# 7seg.net
KiCad netlist of a schematic drawn in Altium Designer
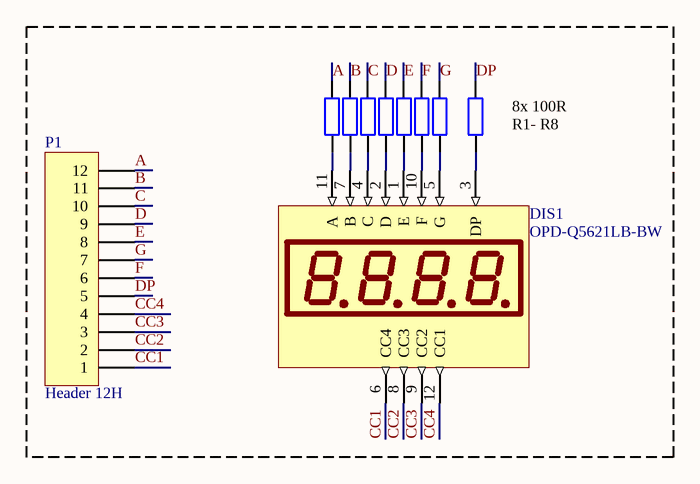
[diagram p0: 7seg.SchDoc]

(export (version "E")
  (design (tool "Eeschema 10.0.6"))
  (components
    (comp (ref "DIS1")
      (value "OPD-Q5621LB-BW")
      (footprint "OPD-Q5621LB-BW")
      (description "Wyświetlacz: LED; 7-segmentowy; 14,2mm; niebieski; 80mcd; katoda")
      (libsource (lib "Library") (part "OPD-Q5621LB-BW"))
    )
    (comp (ref "P1")
      (value "Header 12H")
      (footprint "MA12-1L")
      (description "Header, 12-Pin, Right Angle")
      (libsource (lib "Connectors") (part "Header 12H"))
    )
    (comp (ref "R1")
      (value "100R")
      (footprint "R0805")
      (description "Resistor")
      (libsource (lib "altium-import") (part "root_1_Res_"))
    )
    (comp (ref "R2")
      (value "100R")
      (footprint "R0805")
      (description "Resistor")
      (libsource (lib "altium-import") (part "root_1_Res_"))
    )
    (comp (ref "R3")
      (value "100R")
      (footprint "R0805")
      (description "Resistor")
      (libsource (lib "altium-import") (part "root_1_Res_"))
    )
    (comp (ref "R4")
      (value "100R")
      (footprint "R0805")
      (description "Resistor")
      (libsource (lib "altium-import") (part "root_1_Res_"))
    )
    (comp (ref "R5")
      (value "100R")
      (footprint "R0805")
      (description "Resistor")
      (libsource (lib "altium-import") (part "root_1_Res_"))
    )
    (comp (ref "R6")
      (value "100R")
      (footprint "R0805")
      (description "Resistor")
      (libsource (lib "altium-import") (part "root_1_Res_"))
    )
    (comp (ref "R7")
      (value "100R")
      (footprint "R0805")
      (description "Resistor")
      (libsource (lib "altium-import") (part "root_1_Res_"))
    )
    (comp (ref "R8")
      (value "100R")
      (footprint "R0805")
      (description "Resistor")
      (libsource (lib "altium-import") (part "root_1_Res_"))
    )
  )
  (nets
    (net (code "1") (name "/A") (class "Default")
      (node (ref "P1") (pin "12") (pinfunction "12_12") (pintype "passive"))
      (node (ref "R1") (pin "2") (pinfunction "2_2") (pintype "passive"))
    )
    (net (code "2") (name "/B") (class "Default")
      (node (ref "P1") (pin "11") (pinfunction "11_11") (pintype "passive"))
      (node (ref "R2") (pin "2") (pinfunction "2_2") (pintype "passive"))
    )
    (net (code "3") (name "/C") (class "Default")
      (node (ref "P1") (pin "10") (pinfunction "10_10") (pintype "passive"))
      (node (ref "R3") (pin "2") (pinfunction "2_2") (pintype "passive"))
    )
    (net (code "4") (name "/CC1") (class "Default")
      (node (ref "DIS1") (pin "6") (pinfunction "CC4_6") (pintype "output"))
      (node (ref "P1") (pin "1") (pinfunction "1_1") (pintype "passive"))
    )
    (net (code "5") (name "/CC2") (class "Default")
      (node (ref "DIS1") (pin "8") (pinfunction "CC3_8") (pintype "output"))
      (node (ref "P1") (pin "2") (pinfunction "2_2") (pintype "passive"))
    )
    (net (code "6") (name "/CC3") (class "Default")
      (node (ref "DIS1") (pin "9") (pinfunction "CC2_9") (pintype "output"))
      (node (ref "P1") (pin "3") (pinfunction "3_3") (pintype "passive"))
    )
    (net (code "7") (name "/CC4") (class "Default")
      (node (ref "DIS1") (pin "12") (pinfunction "CC1_12") (pintype "output"))
      (node (ref "P1") (pin "4") (pinfunction "4_4") (pintype "passive"))
    )
    (net (code "8") (name "/D") (class "Default")
      (node (ref "P1") (pin "9") (pinfunction "9_9") (pintype "passive"))
      (node (ref "R4") (pin "2") (pinfunction "2_2") (pintype "passive"))
    )
    (net (code "9") (name "/DP") (class "Default")
      (node (ref "P1") (pin "5") (pinfunction "5_5") (pintype "passive"))
      (node (ref "R8") (pin "2") (pinfunction "2_2") (pintype "passive"))
    )
    (net (code "10") (name "/E") (class "Default")
      (node (ref "P1") (pin "8") (pinfunction "8_8") (pintype "passive"))
      (node (ref "R5") (pin "2") (pinfunction "2_2") (pintype "passive"))
    )
    (net (code "11") (name "/F") (class "Default")
      (node (ref "P1") (pin "6") (pinfunction "6_6") (pintype "passive"))
      (node (ref "R6") (pin "2") (pinfunction "2_2") (pintype "passive"))
    )
    (net (code "12") (name "/G") (class "Default")
      (node (ref "P1") (pin "7") (pinfunction "7_7") (pintype "passive"))
      (node (ref "R7") (pin "2") (pinfunction "2_2") (pintype "passive"))
    )
    (net (code "13") (name "Net-(DIS1-A)") (class "Default")
      (node (ref "DIS1") (pin "11") (pinfunction "A_11") (pintype "input"))
      (node (ref "R1") (pin "1") (pinfunction "1_1") (pintype "passive"))
    )
    (net (code "14") (name "Net-(DIS1-B)") (class "Default")
      (node (ref "DIS1") (pin "7") (pinfunction "B_7") (pintype "input"))
      (node (ref "R2") (pin "1") (pinfunction "1_1") (pintype "passive"))
    )
    (net (code "15") (name "Net-(DIS1-C)") (class "Default")
      (node (ref "DIS1") (pin "4") (pinfunction "C_4") (pintype "input"))
      (node (ref "R3") (pin "1") (pinfunction "1_1") (pintype "passive"))
    )
    (net (code "16") (name "Net-(DIS1-D)") (class "Default")
      (node (ref "DIS1") (pin "2") (pinfunction "D_2") (pintype "input"))
      (node (ref "R4") (pin "1") (pinfunction "1_1") (pintype "passive"))
    )
    (net (code "17") (name "Net-(DIS1-DP)") (class "Default")
      (node (ref "DIS1") (pin "3") (pinfunction "DP_3") (pintype "input"))
      (node (ref "R8") (pin "1") (pinfunction "1_1") (pintype "passive"))
    )
    (net (code "18") (name "Net-(DIS1-E)") (class "Default")
      (node (ref "DIS1") (pin "1") (pinfunction "E_1") (pintype "input"))
      (node (ref "R5") (pin "1") (pinfunction "1_1") (pintype "passive"))
    )
    (net (code "19") (name "Net-(DIS1-F)") (class "Default")
      (node (ref "DIS1") (pin "10") (pinfunction "F_10") (pintype "input"))
      (node (ref "R6") (pin "1") (pinfunction "1_1") (pintype "passive"))
    )
    (net (code "20") (name "Net-(DIS1-G)") (class "Default")
      (node (ref "DIS1") (pin "5") (pinfunction "G_5") (pintype "input"))
      (node (ref "R7") (pin "1") (pinfunction "1_1") (pintype "passive"))
    )
  )
)
